# Breakout_10Pin.net
KiCad netlist of a schematic drawn in EAGLE
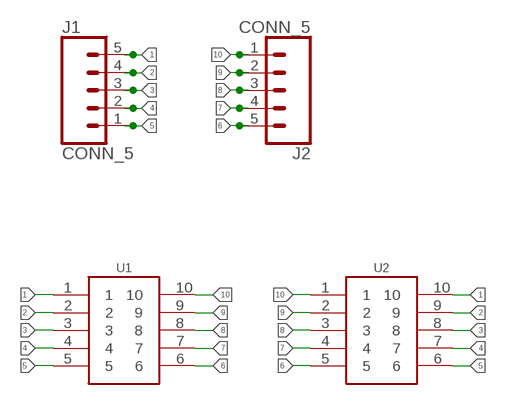
[diagram p0: schematic, sheet 1]

(export (version "E")
  (design (tool "Eeschema 10.0.6"))
  (components
    (comp (ref "J1")
      (value "CONN_5")
      (footprint "eagle-import:1X05")
      (libsource (lib "eagle-import") (part "CONN_5"))
    )
    (comp (ref "J2")
      (value "CONN_5")
      (footprint "eagle-import:1X05")
      (libsource (lib "eagle-import") (part "CONN_5"))
    )
    (comp (ref "U1")
      (value "GEN_10SOIC10")
      (footprint "eagle-import:SO10")
      (libsource (lib "eagle-import") (part "GEN_10SOIC10"))
    )
    (comp (ref "U2")
      (value "GEN_10VSSOP10")
      (footprint "eagle-import:VSSOP_10")
      (libsource (lib "eagle-import") (part "GEN_10VSSOP10"))
    )
  )
  (nets
    (net (code "1") (name "1") (class "Default")
      (node (ref "J1") (pin "5") (pinfunction "5_5") (pintype "passive"))
      (node (ref "U1") (pin "1") (pinfunction "1_1") (pintype "bidirectional"))
      (node (ref "U2") (pin "10") (pinfunction "10_10") (pintype "bidirectional"))
    )
    (net (code "2") (name "2") (class "Default")
      (node (ref "J1") (pin "4") (pinfunction "4_4") (pintype "passive"))
      (node (ref "U1") (pin "2") (pinfunction "2_2") (pintype "bidirectional"))
      (node (ref "U2") (pin "9") (pinfunction "9_9") (pintype "bidirectional"))
    )
    (net (code "3") (name "3") (class "Default")
      (node (ref "J1") (pin "3") (pinfunction "3_3") (pintype "passive"))
      (node (ref "U1") (pin "3") (pinfunction "3_3") (pintype "bidirectional"))
      (node (ref "U2") (pin "8") (pinfunction "8_8") (pintype "bidirectional"))
    )
    (net (code "4") (name "4") (class "Default")
      (node (ref "J1") (pin "2") (pinfunction "2_2") (pintype "passive"))
      (node (ref "U1") (pin "4") (pinfunction "4_4") (pintype "bidirectional"))
      (node (ref "U2") (pin "7") (pinfunction "7_7") (pintype "bidirectional"))
    )
    (net (code "5") (name "5") (class "Default")
      (node (ref "J1") (pin "1") (pinfunction "1_1") (pintype "passive"))
      (node (ref "U1") (pin "5") (pinfunction "5_5") (pintype "bidirectional"))
      (node (ref "U2") (pin "6") (pinfunction "6_6") (pintype "bidirectional"))
    )
    (net (code "6") (name "6") (class "Default")
      (node (ref "J2") (pin "5") (pinfunction "5_5") (pintype "passive"))
      (node (ref "U1") (pin "6") (pinfunction "6_6") (pintype "bidirectional"))
      (node (ref "U2") (pin "5") (pinfunction "5_5") (pintype "bidirectional"))
    )
    (net (code "7") (name "7") (class "Default")
      (node (ref "J2") (pin "4") (pinfunction "4_4") (pintype "passive"))
      (node (ref "U1") (pin "7") (pinfunction "7_7") (pintype "bidirectional"))
      (node (ref "U2") (pin "4") (pinfunction "4_4") (pintype "bidirectional"))
    )
    (net (code "8") (name "8") (class "Default")
      (node (ref "J2") (pin "3") (pinfunction "3_3") (pintype "passive"))
      (node (ref "U1") (pin "8") (pinfunction "8_8") (pintype "bidirectional"))
      (node (ref "U2") (pin "3") (pinfunction "3_3") (pintype "bidirectional"))
    )
    (net (code "9") (name "9") (class "Default")
      (node (ref "J2") (pin "2") (pinfunction "2_2") (pintype "passive"))
      (node (ref "U1") (pin "9") (pinfunction "9_9") (pintype "bidirectional"))
      (node (ref "U2") (pin "2") (pinfunction "2_2") (pintype "bidirectional"))
    )
    (net (code "10") (name "10") (class "Default")
      (node (ref "J2") (pin "1") (pinfunction "1_1") (pintype "passive"))
      (node (ref "U1") (pin "10") (pinfunction "10_10") (pintype "bidirectional"))
      (node (ref "U2") (pin "1") (pinfunction "1_1") (pintype "bidirectional"))
    )
  )
)
